# Display.net
KiCad netlist of a schematic drawn in EAGLE
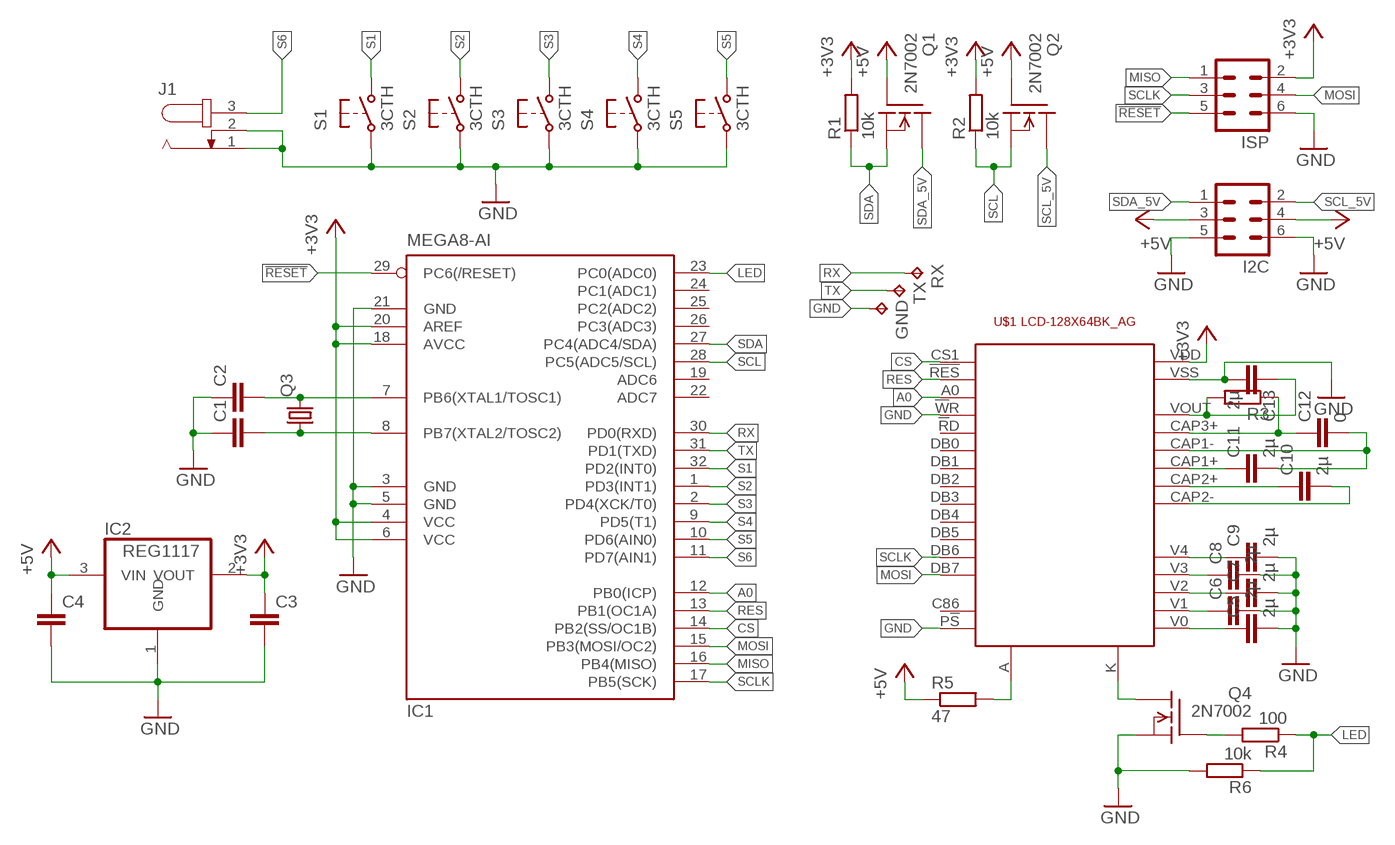
[diagram p0: schematic, sheet 1]

(export (version "E")
  (design (tool "Eeschema 10.0.6"))
  (components
    (comp (ref "C1")
      (value "C-EUC0805K")
      (footprint "eagle-import:C0805K")
      (libsource (lib "eagle-import") (part "C-EUC0805K"))
    )
    (comp (ref "C2")
      (value "C-EUC0805K")
      (footprint "eagle-import:C0805K")
      (libsource (lib "eagle-import") (part "C-EUC0805K"))
    )
    (comp (ref "C3")
      (value "C-EUC0805K")
      (footprint "eagle-import:C0805K")
      (libsource (lib "eagle-import") (part "C-EUC0805K"))
    )
    (comp (ref "C4")
      (value "C-EUC0805K")
      (footprint "eagle-import:C0805K")
      (libsource (lib "eagle-import") (part "C-EUC0805K"))
    )
    (comp (ref "C5")
      (value "2µ")
      (footprint "eagle-import:C0805K")
      (libsource (lib "eagle-import") (part "C-EUC0805K"))
    )
    (comp (ref "C6")
      (value "2µ")
      (footprint "eagle-import:C0805K")
      (libsource (lib "eagle-import") (part "C-EUC0805K"))
    )
    (comp (ref "C7")
      (value "2µ")
      (footprint "eagle-import:C0805K")
      (libsource (lib "eagle-import") (part "C-EUC0805K"))
    )
    (comp (ref "C8")
      (value "2µ")
      (footprint "eagle-import:C0805K")
      (libsource (lib "eagle-import") (part "C-EUC0805K"))
    )
    (comp (ref "C9")
      (value "2µ")
      (footprint "eagle-import:C0805K")
      (libsource (lib "eagle-import") (part "C-EUC0805K"))
    )
    (comp (ref "C10")
      (value "2µ")
      (footprint "eagle-import:C0805K")
      (libsource (lib "eagle-import") (part "C-EUC0805K"))
    )
    (comp (ref "C11")
      (value "2µ")
      (footprint "eagle-import:C0805K")
      (libsource (lib "eagle-import") (part "C-EUC0805K"))
    )
    (comp (ref "C12")
      (value "0")
      (footprint "eagle-import:C0805K")
      (libsource (lib "eagle-import") (part "C-EUC0805K"))
    )
    (comp (ref "C13")
      (value "2µ")
      (footprint "eagle-import:C0805K")
      (libsource (lib "eagle-import") (part "C-EUC0805K"))
    )
    (comp (ref "GND")
      (value "TPPAD1-13")
      (footprint "eagle-import:P1-13")
      (libsource (lib "eagle-import") (part "TPPAD1-13"))
    )
    (comp (ref "I2C")
      (value "ML6")
      (footprint "eagle-import:ML6")
      (libsource (lib "eagle-import") (part "ML6"))
    )
    (comp (ref "IC1")
      (value "MEGA8-AI")
      (footprint "eagle-import:TQFP32-08")
      (fields (field (name "MPN") "ATMEGA8-16AU"))
      (libsource (lib "eagle-import") (part "MEGA8-AI"))
    )
    (comp (ref "IC2")
      (value "REG1117")
      (footprint "eagle-import:SOT223")
      (libsource (lib "eagle-import") (part "REG1117"))
    )
    (comp (ref "ISP")
      (value "ML6")
      (footprint "eagle-import:ML6")
      (libsource (lib "eagle-import") (part "ML6"))
    )
    (comp (ref "J1")
      (value "JACK-PLUG0")
      (footprint "eagle-import:SPC4077")
      (libsource (lib "eagle-import") (part "JACK-PLUG0"))
    )
    (comp (ref "Q1")
      (value "2N7002")
      (footprint "eagle-import:SOT23")
      (libsource (lib "eagle-import") (part "2N7002"))
    )
    (comp (ref "Q2")
      (value "2N7002")
      (footprint "eagle-import:SOT23")
      (libsource (lib "eagle-import") (part "2N7002"))
    )
    (comp (ref "Q3")
      (value "CRYSTALHC49UP")
      (footprint "eagle-import:HC49UP")
      (libsource (lib "eagle-import") (part "CRYSTALHC49UP"))
    )
    (comp (ref "Q4")
      (value "2N7002")
      (footprint "eagle-import:SOT23")
      (libsource (lib "eagle-import") (part "2N7002"))
    )
    (comp (ref "R1")
      (value "10k")
      (footprint "eagle-import:R0805")
      (libsource (lib "eagle-import") (part "R-EU_R0805"))
    )
    (comp (ref "R2")
      (value "10k")
      (footprint "eagle-import:R0805")
      (libsource (lib "eagle-import") (part "R-EU_R0805"))
    )
    (comp (ref "R3")
      (value "R-EU_R0805")
      (footprint "eagle-import:R0805")
      (libsource (lib "eagle-import") (part "R-EU_R0805"))
    )
    (comp (ref "R4")
      (value "100")
      (footprint "eagle-import:R0805")
      (libsource (lib "eagle-import") (part "R-EU_R0805"))
    )
    (comp (ref "R5")
      (value "47")
      (footprint "eagle-import:0207_10")
      (libsource (lib "eagle-import") (part "R-EU_0207/10"))
    )
    (comp (ref "R6")
      (value "10k")
      (footprint "eagle-import:R0805")
      (libsource (lib "eagle-import") (part "R-EU_R0805"))
    )
    (comp (ref "RX")
      (value "TPPAD1-13")
      (footprint "eagle-import:P1-13")
      (libsource (lib "eagle-import") (part "TPPAD1-13"))
    )
    (comp (ref "S1")
      (value "3CTH")
      (footprint "eagle-import:3CTH")
      (libsource (lib "eagle-import") (part "3CTH"))
    )
    (comp (ref "S2")
      (value "3CTH")
      (footprint "eagle-import:3CTH")
      (libsource (lib "eagle-import") (part "3CTH"))
    )
    (comp (ref "S3")
      (value "3CTH")
      (footprint "eagle-import:3CTH")
      (libsource (lib "eagle-import") (part "3CTH"))
    )
    (comp (ref "S4")
      (value "3CTH")
      (footprint "eagle-import:3CTH")
      (libsource (lib "eagle-import") (part "3CTH"))
    )
    (comp (ref "S5")
      (value "3CTH")
      (footprint "eagle-import:3CTH")
      (libsource (lib "eagle-import") (part "3CTH"))
    )
    (comp (ref "TX")
      (value "TPPAD1-13")
      (footprint "eagle-import:P1-13")
      (libsource (lib "eagle-import") (part "TPPAD1-13"))
    )
    (comp (ref "U$1")
      (value "LCD-128X64BK_AG")
      (footprint "eagle-import:LCD-128X64BK_AG")
      (libsource (lib "eagle-import") (part "LCD-128X64BK_AG"))
    )
  )
  (nets
    (net (code "1") (name "+3V3") (class "Default")
      (node (ref "C3") (pin "1") (pinfunction "1_1") (pintype "passive"))
      (node (ref "IC1") (pin "18") (pinfunction "AVCC_18") (pintype "power_in"))
      (node (ref "IC1") (pin "20") (pinfunction "AREF_20") (pintype "passive"))
      (node (ref "IC1") (pin "4") (pinfunction "VCC_4") (pintype "power_in"))
      (node (ref "IC1") (pin "6") (pinfunction "VCC_6") (pintype "power_in"))
      (node (ref "IC2") (pin "2") (pinfunction "VOUT_2") (pintype "output"))
      (node (ref "ISP") (pin "2") (pinfunction "2_2") (pintype "passive"))
      (node (ref "R1") (pin "2") (pinfunction "2_2") (pintype "passive"))
      (node (ref "R2") (pin "2") (pinfunction "2_2") (pintype "passive"))
      (node (ref "U$1") (pin "VDD") (pinfunction "VDD_VDD") (pintype "bidirectional"))
    )
    (net (code "2") (name "+5V") (class "Default")
      (node (ref "C4") (pin "1") (pinfunction "1_1") (pintype "passive"))
      (node (ref "I2C") (pin "3") (pinfunction "3_3") (pintype "passive"))
      (node (ref "I2C") (pin "4") (pinfunction "4_4") (pintype "passive"))
      (node (ref "IC2") (pin "3") (pinfunction "VIN_3") (pintype "input"))
      (node (ref "Q1") (pin "1") (pinfunction "G_1") (pintype "passive"))
      (node (ref "Q2") (pin "1") (pinfunction "G_1") (pintype "passive"))
      (node (ref "R5") (pin "1") (pinfunction "1_1") (pintype "passive"))
    )
    (net (code "3") (name "/~{RESET}") (class "Default")
      (node (ref "IC1") (pin "29") (pinfunction "PC6(/RESET)_29") (pintype "bidirectional"))
      (node (ref "ISP") (pin "5") (pinfunction "5_5") (pintype "passive"))
    )
    (net (code "4") (name "A0") (class "Default")
      (node (ref "IC1") (pin "12") (pinfunction "PB0(ICP)_12") (pintype "bidirectional"))
      (node (ref "U$1") (pin "A0") (pinfunction "A0_A0") (pintype "bidirectional"))
    )
    (net (code "5") (name "CS") (class "Default")
      (node (ref "IC1") (pin "14") (pinfunction "PB2(SS/OC1B)_14") (pintype "bidirectional"))
      (node (ref "U$1") (pin "CS1") (pinfunction "CS1_CS1") (pintype "bidirectional"))
    )
    (net (code "6") (name "GND") (class "Default")
      (node (ref "C1") (pin "1") (pinfunction "1_1") (pintype "passive"))
      (node (ref "C13") (pin "2") (pinfunction "2_2") (pintype "passive"))
      (node (ref "C2") (pin "1") (pinfunction "1_1") (pintype "passive"))
      (node (ref "C3") (pin "2") (pinfunction "2_2") (pintype "passive"))
      (node (ref "C4") (pin "2") (pinfunction "2_2") (pintype "passive"))
      (node (ref "C5") (pin "2") (pinfunction "2_2") (pintype "passive"))
      (node (ref "C6") (pin "2") (pinfunction "2_2") (pintype "passive"))
      (node (ref "C7") (pin "2") (pinfunction "2_2") (pintype "passive"))
      (node (ref "C8") (pin "2") (pinfunction "2_2") (pintype "passive"))
      (node (ref "C9") (pin "2") (pinfunction "2_2") (pintype "passive"))
      (node (ref "GND") (pin "TP") (pinfunction "TP_TP") (pintype "input"))
      (node (ref "I2C") (pin "5") (pinfunction "5_5") (pintype "passive"))
      (node (ref "I2C") (pin "6") (pinfunction "6_6") (pintype "passive"))
      (node (ref "IC1") (pin "21") (pinfunction "GND_21") (pintype "power_in"))
      (node (ref "IC1") (pin "3") (pinfunction "GND_3") (pintype "power_in"))
      (node (ref "IC1") (pin "5") (pinfunction "GND_5") (pintype "power_in"))
      (node (ref "IC2") (pin "1") (pinfunction "GND_1") (pintype "power_in"))
      (node (ref "ISP") (pin "6") (pinfunction "6_6") (pintype "passive"))
      (node (ref "J1") (pin "1") (pinfunction "1_1") (pintype "passive"))
      (node (ref "J1") (pin "2") (pinfunction "2_2") (pintype "passive"))
      (node (ref "Q4") (pin "2") (pinfunction "S_2") (pintype "passive"))
      (node (ref "R6") (pin "2") (pinfunction "2_2") (pintype "passive"))
      (node (ref "S1") (pin "3") (pinfunction "P_3") (pintype "passive"))
      (node (ref "S1") (pin "4") (pinfunction "P_4") (pintype "passive"))
      (node (ref "S2") (pin "3") (pinfunction "P_3") (pintype "passive"))
      (node (ref "S2") (pin "4") (pinfunction "P_4") (pintype "passive"))
      (node (ref "S3") (pin "3") (pinfunction "P_3") (pintype "passive"))
      (node (ref "S3") (pin "4") (pinfunction "P_4") (pintype "passive"))
      (node (ref "S4") (pin "3") (pinfunction "P_3") (pintype "passive"))
      (node (ref "S4") (pin "4") (pinfunction "P_4") (pintype "passive"))
      (node (ref "S5") (pin "3") (pinfunction "P_3") (pintype "passive"))
      (node (ref "S5") (pin "4") (pinfunction "P_4") (pintype "passive"))
      (node (ref "U$1") (pin "!W!R") (pinfunction "~{W}R_!W!R") (pintype "bidirectional"))
      (node (ref "U$1") (pin "P!S") (pinfunction "P~{S}_P!S") (pintype "bidirectional"))
      (node (ref "U$1") (pin "VSS") (pinfunction "VSS_VSS") (pintype "bidirectional"))
    )
    (net (code "7") (name "LED") (class "Default")
      (node (ref "IC1") (pin "23") (pinfunction "PC0(ADC0)_23") (pintype "bidirectional"))
      (node (ref "R4") (pin "1") (pinfunction "1_1") (pintype "passive"))
      (node (ref "R6") (pin "1") (pinfunction "1_1") (pintype "passive"))
    )
    (net (code "8") (name "MISO") (class "Default")
      (node (ref "IC1") (pin "16") (pinfunction "PB4(MISO)_16") (pintype "bidirectional"))
      (node (ref "ISP") (pin "1") (pinfunction "1_1") (pintype "passive"))
    )
    (net (code "9") (name "MOSI") (class "Default")
      (node (ref "IC1") (pin "15") (pinfunction "PB3(MOSI/OC2)_15") (pintype "bidirectional"))
      (node (ref "ISP") (pin "4") (pinfunction "4_4") (pintype "passive"))
      (node (ref "U$1") (pin "DB7") (pinfunction "DB7_DB7") (pintype "bidirectional"))
    )
    (net (code "10") (name "Net-(C5-Pad1)") (class "Default")
      (node (ref "C5") (pin "1") (pinfunction "1_1") (pintype "passive"))
      (node (ref "U$1") (pin "V0") (pinfunction "V0_V0") (pintype "bidirectional"))
    )
    (net (code "11") (name "Net-(C6-Pad1)") (class "Default")
      (node (ref "C6") (pin "1") (pinfunction "1_1") (pintype "passive"))
      (node (ref "U$1") (pin "V1") (pinfunction "V1_V1") (pintype "bidirectional"))
    )
    (net (code "12") (name "Net-(C7-Pad1)") (class "Default")
      (node (ref "C7") (pin "1") (pinfunction "1_1") (pintype "passive"))
      (node (ref "U$1") (pin "V2") (pinfunction "V2_V2") (pintype "bidirectional"))
    )
    (net (code "13") (name "Net-(C8-Pad1)") (class "Default")
      (node (ref "C8") (pin "1") (pinfunction "1_1") (pintype "passive"))
      (node (ref "U$1") (pin "V3") (pinfunction "V3_V3") (pintype "bidirectional"))
    )
    (net (code "14") (name "Net-(C9-Pad1)") (class "Default")
      (node (ref "C9") (pin "1") (pinfunction "1_1") (pintype "passive"))
      (node (ref "U$1") (pin "V4") (pinfunction "V4_V4") (pintype "bidirectional"))
    )
    (net (code "15") (name "Net-(C10-Pad1)") (class "Default")
      (node (ref "C10") (pin "1") (pinfunction "1_1") (pintype "passive"))
      (node (ref "U$1") (pin "CAP2+") (pinfunction "CAP2+_CAP2+") (pintype "bidirectional"))
    )
    (net (code "16") (name "Net-(C10-Pad2)") (class "Default")
      (node (ref "C10") (pin "2") (pinfunction "2_2") (pintype "passive"))
      (node (ref "U$1") (pin "CAP2-") (pinfunction "CAP2-_CAP2-") (pintype "bidirectional"))
    )
    (net (code "17") (name "Net-(C11-Pad1)") (class "Default")
      (node (ref "C11") (pin "1") (pinfunction "1_1") (pintype "passive"))
      (node (ref "U$1") (pin "CAP1+") (pinfunction "CAP1+_CAP1+") (pintype "bidirectional"))
    )
    (net (code "18") (name "Net-(C11-Pad2)") (class "Default")
      (node (ref "C11") (pin "2") (pinfunction "2_2") (pintype "passive"))
      (node (ref "C12") (pin "2") (pinfunction "2_2") (pintype "passive"))
      (node (ref "U$1") (pin "CAP1-") (pinfunction "CAP1-_CAP1-") (pintype "bidirectional"))
    )
    (net (code "19") (name "Net-(C12-Pad1)") (class "Default")
      (node (ref "C12") (pin "1") (pinfunction "1_1") (pintype "passive"))
      (node (ref "R3") (pin "1") (pinfunction "1_1") (pintype "passive"))
      (node (ref "U$1") (pin "CAP3+") (pinfunction "CAP3+_CAP3+") (pintype "bidirectional"))
    )
    (net (code "20") (name "Net-(C13-Pad1)") (class "Default")
      (node (ref "C13") (pin "1") (pinfunction "1_1") (pintype "passive"))
      (node (ref "R3") (pin "2") (pinfunction "2_2") (pintype "passive"))
      (node (ref "U$1") (pin "VOUT") (pinfunction "VOUT_VOUT") (pintype "bidirectional"))
    )
    (net (code "21") (name "Net-(IC1-PB6(XTAL1{slash}TOSC1))") (class "Default")
      (node (ref "C2") (pin "2") (pinfunction "2_2") (pintype "passive"))
      (node (ref "IC1") (pin "7") (pinfunction "PB6(XTAL1/TOSC1)_7") (pintype "bidirectional"))
      (node (ref "Q3") (pin "2") (pinfunction "2_2") (pintype "passive"))
    )
    (net (code "22") (name "Net-(IC1-PB7(XTAL2{slash}TOSC2))") (class "Default")
      (node (ref "C1") (pin "2") (pinfunction "2_2") (pintype "passive"))
      (node (ref "IC1") (pin "8") (pinfunction "PB7(XTAL2/TOSC2)_8") (pintype "bidirectional"))
      (node (ref "Q3") (pin "1") (pinfunction "1_1") (pintype "passive"))
    )
    (net (code "23") (name "Net-(Q4-D)") (class "Default")
      (node (ref "Q4") (pin "3") (pinfunction "D_3") (pintype "passive"))
      (node (ref "U$1") (pin "K") (pinfunction "K_K") (pintype "bidirectional"))
    )
    (net (code "24") (name "Net-(Q4-G)") (class "Default")
      (node (ref "Q4") (pin "1") (pinfunction "G_1") (pintype "passive"))
      (node (ref "R4") (pin "2") (pinfunction "2_2") (pintype "passive"))
    )
    (net (code "25") (name "Net-(R5-Pad2)") (class "Default")
      (node (ref "R5") (pin "2") (pinfunction "2_2") (pintype "passive"))
      (node (ref "U$1") (pin "A") (pinfunction "A_A") (pintype "bidirectional"))
    )
    (net (code "26") (name "RES") (class "Default")
      (node (ref "IC1") (pin "13") (pinfunction "PB1(OC1A)_13") (pintype "bidirectional"))
      (node (ref "U$1") (pin "!RES") (pinfunction "~{RES}_!RES") (pintype "bidirectional"))
    )
    (net (code "27") (name "RX") (class "Default")
      (node (ref "IC1") (pin "30") (pinfunction "PD0(RXD)_30") (pintype "bidirectional"))
      (node (ref "RX") (pin "TP") (pinfunction "TP_TP") (pintype "input"))
    )
    (net (code "28") (name "S1") (class "Default")
      (node (ref "IC1") (pin "32") (pinfunction "PD2(INT0)_32") (pintype "bidirectional"))
      (node (ref "S1") (pin "1") (pinfunction "S_1") (pintype "passive"))
      (node (ref "S1") (pin "2") (pinfunction "S_2") (pintype "passive"))
    )
    (net (code "29") (name "S2") (class "Default")
      (node (ref "IC1") (pin "1") (pinfunction "PD3(INT1)_1") (pintype "bidirectional"))
      (node (ref "S2") (pin "1") (pinfunction "S_1") (pintype "passive"))
      (node (ref "S2") (pin "2") (pinfunction "S_2") (pintype "passive"))
    )
    (net (code "30") (name "S3") (class "Default")
      (node (ref "IC1") (pin "2") (pinfunction "PD4(XCK/T0)_2") (pintype "bidirectional"))
      (node (ref "S3") (pin "1") (pinfunction "S_1") (pintype "passive"))
      (node (ref "S3") (pin "2") (pinfunction "S_2") (pintype "passive"))
    )
    (net (code "31") (name "S4") (class "Default")
      (node (ref "IC1") (pin "9") (pinfunction "PD5(T1)_9") (pintype "bidirectional"))
      (node (ref "S4") (pin "1") (pinfunction "S_1") (pintype "passive"))
      (node (ref "S4") (pin "2") (pinfunction "S_2") (pintype "passive"))
    )
    (net (code "32") (name "S5") (class "Default")
      (node (ref "IC1") (pin "10") (pinfunction "PD6(AIN0)_10") (pintype "bidirectional"))
      (node (ref "S5") (pin "1") (pinfunction "S_1") (pintype "passive"))
      (node (ref "S5") (pin "2") (pinfunction "S_2") (pintype "passive"))
    )
    (net (code "33") (name "S6") (class "Default")
      (node (ref "IC1") (pin "11") (pinfunction "PD7(AIN1)_11") (pintype "bidirectional"))
      (node (ref "J1") (pin "3") (pinfunction "3_3") (pintype "passive"))
    )
    (net (code "34") (name "SCL") (class "Default")
      (node (ref "IC1") (pin "28") (pinfunction "PC5(ADC5/SCL)_28") (pintype "bidirectional"))
      (node (ref "Q2") (pin "2") (pinfunction "S_2") (pintype "passive"))
      (node (ref "R2") (pin "1") (pinfunction "1_1") (pintype "passive"))
    )
    (net (code "35") (name "SCLK") (class "Default")
      (node (ref "IC1") (pin "17") (pinfunction "PB5(SCK)_17") (pintype "bidirectional"))
      (node (ref "ISP") (pin "3") (pinfunction "3_3") (pintype "passive"))
      (node (ref "U$1") (pin "DB6") (pinfunction "DB6_DB6") (pintype "bidirectional"))
    )
    (net (code "36") (name "SCL_5V") (class "Default")
      (node (ref "I2C") (pin "2") (pinfunction "2_2") (pintype "passive"))
      (node (ref "Q2") (pin "3") (pinfunction "D_3") (pintype "passive"))
    )
    (net (code "37") (name "SDA") (class "Default")
      (node (ref "IC1") (pin "27") (pinfunction "PC4(ADC4/SDA)_27") (pintype "bidirectional"))
      (node (ref "Q1") (pin "2") (pinfunction "S_2") (pintype "passive"))
      (node (ref "R1") (pin "1") (pinfunction "1_1") (pintype "passive"))
    )
    (net (code "38") (name "SDA_5V") (class "Default")
      (node (ref "I2C") (pin "1") (pinfunction "1_1") (pintype "passive"))
      (node (ref "Q1") (pin "3") (pinfunction "D_3") (pintype "passive"))
    )
    (net (code "39") (name "TX") (class "Default")
      (node (ref "IC1") (pin "31") (pinfunction "PD1(TXD)_31") (pintype "bidirectional"))
      (node (ref "TX") (pin "TP") (pinfunction "TP_TP") (pintype "input"))
    )
    (net (code "40") (name "unconnected-(IC1-ADC6-Pad19)") (class "Default")
      (node (ref "IC1") (pin "19") (pinfunction "ADC6_19") (pintype "bidirectional"))
    )
    (net (code "41") (name "unconnected-(IC1-ADC7-Pad22)") (class "Default")
      (node (ref "IC1") (pin "22") (pinfunction "ADC7_22") (pintype "bidirectional"))
    )
    (net (code "42") (name "unconnected-(IC1-PC1(ADC1)-Pad24)") (class "Default")
      (node (ref "IC1") (pin "24") (pinfunction "PC1(ADC1)_24") (pintype "bidirectional"))
    )
    (net (code "43") (name "unconnected-(IC1-PC2(ADC2)-Pad25)") (class "Default")
      (node (ref "IC1") (pin "25") (pinfunction "PC2(ADC2)_25") (pintype "bidirectional"))
    )
    (net (code "44") (name "unconnected-(IC1-PC3(ADC3)-Pad26)") (class "Default")
      (node (ref "IC1") (pin "26") (pinfunction "PC3(ADC3)_26") (pintype "bidirectional"))
    )
    (net (code "45") (name "unconnected-(U$1-PadC86)") (class "Default")
      (node (ref "U$1") (pin "C86") (pinfunction "C86_C86") (pintype "bidirectional"))
    )
    (net (code "46") (name "unconnected-(U$1-PadDB0)") (class "Default")
      (node (ref "U$1") (pin "DB0") (pinfunction "DB0_DB0") (pintype "bidirectional"))
    )
    (net (code "47") (name "unconnected-(U$1-PadDB1)") (class "Default")
      (node (ref "U$1") (pin "DB1") (pinfunction "DB1_DB1") (pintype "bidirectional"))
    )
    (net (code "48") (name "unconnected-(U$1-PadDB2)") (class "Default")
      (node (ref "U$1") (pin "DB2") (pinfunction "DB2_DB2") (pintype "bidirectional"))
    )
    (net (code "49") (name "unconnected-(U$1-PadDB3)") (class "Default")
      (node (ref "U$1") (pin "DB3") (pinfunction "DB3_DB3") (pintype "bidirectional"))
    )
    (net (code "50") (name "unconnected-(U$1-PadDB4)") (class "Default")
      (node (ref "U$1") (pin "DB4") (pinfunction "DB4_DB4") (pintype "bidirectional"))
    )
    (net (code "51") (name "unconnected-(U$1-PadDB5)") (class "Default")
      (node (ref "U$1") (pin "DB5") (pinfunction "DB5_DB5") (pintype "bidirectional"))
    )
    (net (code "52") (name "unconnected-(U$1-{slash}RD-Pad!R!D)") (class "Default")
      (node (ref "U$1") (pin "!R!D") (pinfunction "/RD_!R!D") (pintype "bidirectional"))
    )
  )
)
